# PlacaHalls.net
KiCad netlist of a schematic drawn in Altium Designer
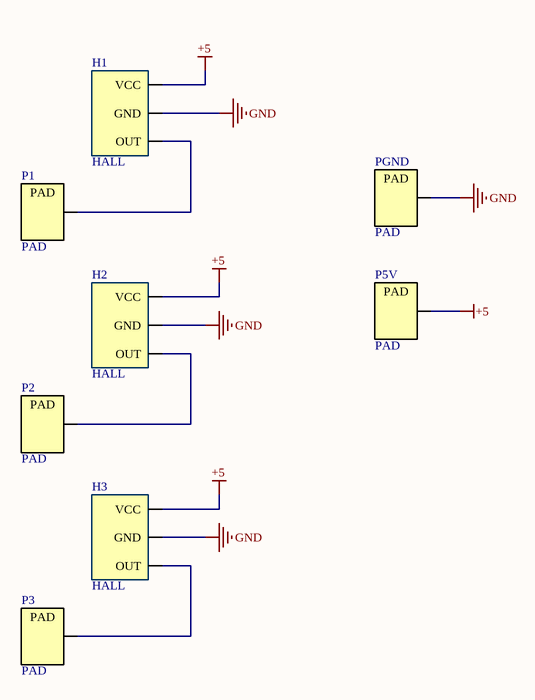
[diagram p0: PlacaHalls.SchDoc]

(export (version "E")
  (design (tool "Eeschema 10.0.6"))
  (components
    (comp (ref "H1")
      (value "HALL")
      (footprint "Hall_Sensor")
      (description "HALL SENSOR")
      (libsource (lib "PlacaHallsLib") (part "HALL"))
    )
    (comp (ref "H2")
      (value "HALL")
      (footprint "Hall_Sensor")
      (description "HALL SENSOR")
      (libsource (lib "PlacaHallsLib") (part "HALL"))
    )
    (comp (ref "H3")
      (value "HALL")
      (footprint "Hall_Sensor")
      (description "HALL SENSOR")
      (libsource (lib "PlacaHallsLib") (part "HALL"))
    )
    (comp (ref "P1") (value "PAD") (footprint "PAD") (libsource (lib "PlacaHallsLib") (part "PAD")))
    (comp (ref "P2") (value "PAD") (footprint "PAD") (libsource (lib "PlacaHallsLib") (part "PAD")))
    (comp (ref "P3") (value "PAD") (footprint "PAD") (libsource (lib "PlacaHallsLib") (part "PAD")))
    (comp (ref "P5V") (value "PAD") (footprint "PAD") (libsource (lib "PlacaHallsLib") (part "PAD")))
    (comp (ref "PGND") (value "PAD") (footprint "PAD") (libsource (lib "PlacaHallsLib") (part "PAD")))
  )
  (nets
    (net (code "1") (name "+5") (class "Default")
      (node (ref "H1") (pin "1") (pinfunction "VCC_1") (pintype "passive"))
      (node (ref "H2") (pin "1") (pinfunction "VCC_1") (pintype "passive"))
      (node (ref "H3") (pin "1") (pinfunction "VCC_1") (pintype "passive"))
      (node (ref "P5V") (pin "1") (pinfunction "PD_1") (pintype "passive"))
    )
    (net (code "2") (name "GND") (class "Default")
      (node (ref "H1") (pin "2") (pinfunction "GND_2") (pintype "passive"))
      (node (ref "H2") (pin "2") (pinfunction "GND_2") (pintype "passive"))
      (node (ref "H3") (pin "2") (pinfunction "GND_2") (pintype "passive"))
      (node (ref "PGND") (pin "1") (pinfunction "PD_1") (pintype "passive"))
    )
    (net (code "3") (name "Net-(H1-OUT)") (class "Default")
      (node (ref "H1") (pin "3") (pinfunction "OUT_3") (pintype "passive"))
      (node (ref "P1") (pin "1") (pinfunction "PD_1") (pintype "passive"))
    )
    (net (code "4") (name "Net-(H2-OUT)") (class "Default")
      (node (ref "H2") (pin "3") (pinfunction "OUT_3") (pintype "passive"))
      (node (ref "P2") (pin "1") (pinfunction "PD_1") (pintype "passive"))
    )
    (net (code "5") (name "Net-(H3-OUT)") (class "Default")
      (node (ref "H3") (pin "3") (pinfunction "OUT_3") (pintype "passive"))
      (node (ref "P3") (pin "1") (pinfunction "PD_1") (pintype "passive"))
    )
  )
)
